# P3_MS.net
KiCad netlist of a schematic drawn in Altium Designer
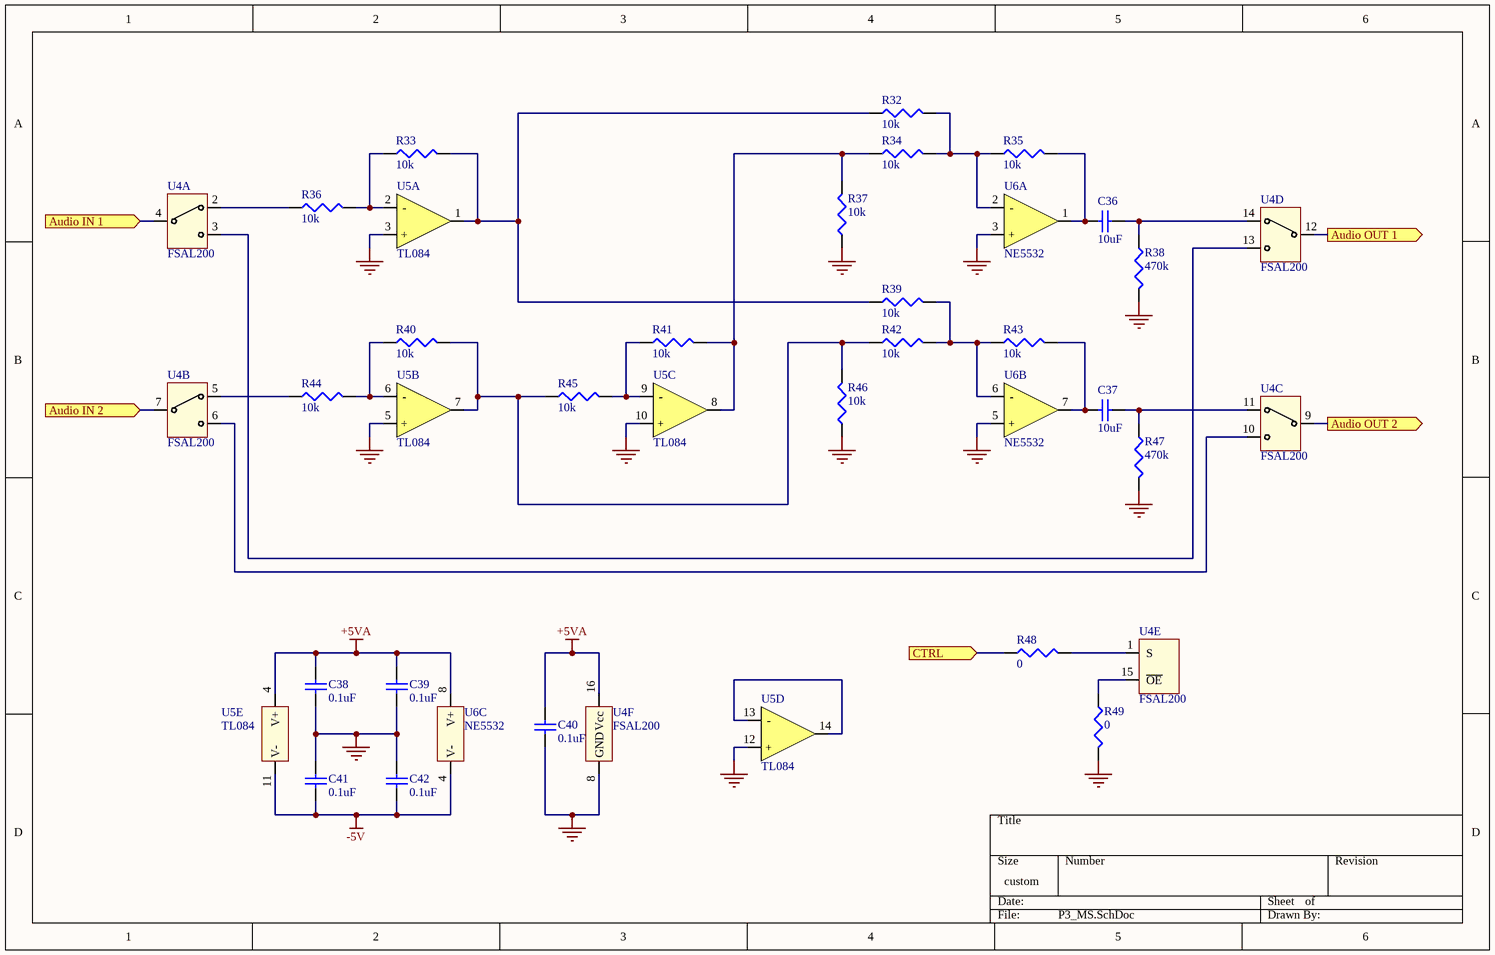
[diagram p0: P3_MS.SchDoc]

(export (version "E")
  (design (tool "Eeschema 10.0.6"))
  (components
    (comp (ref "C36")
      (value "10uF")
      (footprint "CAP 0603 (1608 metric)")
      (description "Capacitor (Semiconductor SIM Model)")
      (libsource (lib "Miscellaneous Devices") (part "Cap Semi"))
    )
    (comp (ref "C37")
      (value "10uF")
      (footprint "CAP 0603 (1608 metric)")
      (description "Capacitor (Semiconductor SIM Model)")
      (libsource (lib "Miscellaneous Devices") (part "Cap Semi"))
    )
    (comp (ref "C38")
      (value "0.1uF")
      (footprint "CAP 0603 (1608 metric)")
      (description "Capacitor (Semiconductor SIM Model)")
      (libsource (lib "Miscellaneous Devices") (part "Cap Semi"))
    )
    (comp (ref "C39")
      (value "0.1uF")
      (footprint "CAP 0603 (1608 metric)")
      (description "Capacitor (Semiconductor SIM Model)")
      (libsource (lib "Miscellaneous Devices") (part "Cap Semi"))
    )
    (comp (ref "C40")
      (value "0.1uF")
      (footprint "CAP 0603 (1608 metric)")
      (description "Capacitor (Semiconductor SIM Model)")
      (libsource (lib "Miscellaneous Devices") (part "Cap Semi"))
    )
    (comp (ref "C41")
      (value "0.1uF")
      (footprint "CAP 0603 (1608 metric)")
      (description "Capacitor (Semiconductor SIM Model)")
      (libsource (lib "Miscellaneous Devices") (part "Cap Semi"))
    )
    (comp (ref "C42")
      (value "0.1uF")
      (footprint "CAP 0603 (1608 metric)")
      (description "Capacitor (Semiconductor SIM Model)")
      (libsource (lib "Miscellaneous Devices") (part "Cap Semi"))
    )
    (comp (ref "R32")
      (value "10k")
      (footprint "RES 0603 (1608 metric)")
      (description "Resistor")
      (libsource (lib "Miscellaneous Devices") (part "Res3"))
    )
    (comp (ref "R33")
      (value "10k")
      (footprint "RES 0603 (1608 metric)")
      (description "Resistor")
      (libsource (lib "Miscellaneous Devices") (part "Res3"))
    )
    (comp (ref "R34")
      (value "10k")
      (footprint "RES 0603 (1608 metric)")
      (description "Resistor")
      (libsource (lib "Miscellaneous Devices") (part "Res3"))
    )
    (comp (ref "R35")
      (value "10k")
      (footprint "RES 0603 (1608 metric)")
      (description "Resistor")
      (libsource (lib "Miscellaneous Devices") (part "Res3"))
    )
    (comp (ref "R36")
      (value "10k")
      (footprint "RES 0603 (1608 metric)")
      (description "Resistor")
      (libsource (lib "Miscellaneous Devices") (part "Res3"))
    )
    (comp (ref "R37")
      (value "10k")
      (footprint "RES 0603 (1608 metric)")
      (description "Resistor")
      (libsource (lib "Miscellaneous Devices") (part "Res3"))
    )
    (comp (ref "R38")
      (value "470k")
      (footprint "RES 0603 (1608 metric)")
      (description "Resistor")
      (libsource (lib "Miscellaneous Devices") (part "Res3"))
    )
    (comp (ref "R39")
      (value "10k")
      (footprint "RES 0603 (1608 metric)")
      (description "Resistor")
      (libsource (lib "Miscellaneous Devices") (part "Res3"))
    )
    (comp (ref "R40")
      (value "10k")
      (footprint "RES 0603 (1608 metric)")
      (description "Resistor")
      (libsource (lib "Miscellaneous Devices") (part "Res3"))
    )
    (comp (ref "R41")
      (value "10k")
      (footprint "RES 0603 (1608 metric)")
      (description "Resistor")
      (libsource (lib "Miscellaneous Devices") (part "Res3"))
    )
    (comp (ref "R42")
      (value "10k")
      (footprint "RES 0603 (1608 metric)")
      (description "Resistor")
      (libsource (lib "Miscellaneous Devices") (part "Res3"))
    )
    (comp (ref "R43")
      (value "10k")
      (footprint "RES 0603 (1608 metric)")
      (description "Resistor")
      (libsource (lib "Miscellaneous Devices") (part "Res3"))
    )
    (comp (ref "R44")
      (value "10k")
      (footprint "RES 0603 (1608 metric)")
      (description "Resistor")
      (libsource (lib "Miscellaneous Devices") (part "Res3"))
    )
    (comp (ref "R45")
      (value "10k")
      (footprint "RES 0603 (1608 metric)")
      (description "Resistor")
      (libsource (lib "Miscellaneous Devices") (part "Res3"))
    )
    (comp (ref "R46")
      (value "10k")
      (footprint "RES 0603 (1608 metric)")
      (description "Resistor")
      (libsource (lib "Miscellaneous Devices") (part "Res3"))
    )
    (comp (ref "R47")
      (value "470k")
      (footprint "RES 0603 (1608 metric)")
      (description "Resistor")
      (libsource (lib "Miscellaneous Devices") (part "Res3"))
    )
    (comp (ref "R48")
      (value "0")
      (footprint "RES 0603 (1608 metric)")
      (description "Resistor")
      (libsource (lib "Miscellaneous Devices") (part "Res3"))
    )
    (comp (ref "R49")
      (value "0")
      (footprint "RES 0603 (1608 metric)")
      (description "Resistor")
      (libsource (lib "Miscellaneous Devices") (part "Res3"))
    )
    (comp (ref "U4")
      (value "FSAL200")
      (description "Quad 2:1 Multiplexer")
      (libsource (lib "FilterPoC") (part "FSAL200"))
    )
    (comp (ref "U5")
      (value "TL084")
      (description "Quad Audio OpAmp")
      (libsource (lib "FilterPoC") (part "TL084"))
    )
    (comp (ref "U6")
      (value "NE5532")
      (description "Dual Audio OpAmp")
      (libsource (lib "FilterPoC") (part "NE5532"))
    )
  )
  (nets
    (net (code "1") (name "+5VA") (class "Default")
      (node (ref "C38") (pin "1") (pinfunction "1_1") (pintype "passive"))
      (node (ref "C39") (pin "1") (pinfunction "1_1") (pintype "passive"))
      (node (ref "C40") (pin "1") (pinfunction "1_1") (pintype "passive"))
      (node (ref "U4") (pin "16") (pinfunction "Vcc_16") (pintype "power_in"))
      (node (ref "U5") (pin "4") (pinfunction "V+_4") (pintype "power_in"))
      (node (ref "U6") (pin "8") (pinfunction "V+_8") (pintype "power_in"))
    )
    (net (code "2") (name "-5V") (class "Default")
      (node (ref "C41") (pin "2") (pinfunction "2_2") (pintype "passive"))
      (node (ref "C42") (pin "2") (pinfunction "2_2") (pintype "passive"))
      (node (ref "U5") (pin "11") (pinfunction "V-_11") (pintype "power_in"))
      (node (ref "U6") (pin "4") (pinfunction "V-_4") (pintype "power_in"))
    )
    (net (code "3") (name "/Audio IN 1") (class "Default")
      (node (ref "U4") (pin "4") (pinfunction "A_4") (pintype "passive"))
    )
    (net (code "4") (name "/Audio IN 2") (class "Default")
      (node (ref "U4") (pin "7") (pinfunction "A_7") (pintype "passive"))
    )
    (net (code "5") (name "/Audio OUT 1") (class "Default")
      (node (ref "U4") (pin "12") (pinfunction "A_12") (pintype "passive"))
    )
    (net (code "6") (name "/Audio OUT 2") (class "Default")
      (node (ref "U4") (pin "9") (pinfunction "A_9") (pintype "passive"))
    )
    (net (code "7") (name "/CTRL") (class "Default")
      (node (ref "R48") (pin "1") (pinfunction "1_1") (pintype "passive"))
    )
    (net (code "8") (name "GND") (class "Default")
      (node (ref "C38") (pin "2") (pinfunction "2_2") (pintype "passive"))
      (node (ref "C39") (pin "2") (pinfunction "2_2") (pintype "passive"))
      (node (ref "C40") (pin "2") (pinfunction "2_2") (pintype "passive"))
      (node (ref "C41") (pin "1") (pinfunction "1_1") (pintype "passive"))
      (node (ref "C42") (pin "1") (pinfunction "1_1") (pintype "passive"))
      (node (ref "R37") (pin "1") (pinfunction "1_1") (pintype "passive"))
      (node (ref "R38") (pin "2") (pinfunction "2_2") (pintype "passive"))
      (node (ref "R46") (pin "1") (pinfunction "1_1") (pintype "passive"))
      (node (ref "R47") (pin "2") (pinfunction "2_2") (pintype "passive"))
      (node (ref "R49") (pin "2") (pinfunction "2_2") (pintype "passive"))
      (node (ref "U4") (pin "8") (pinfunction "GND_8") (pintype "power_in"))
      (node (ref "U5") (pin "10") (pinfunction "+_10") (pintype "passive"))
      (node (ref "U5") (pin "12") (pinfunction "+_12") (pintype "passive"))
      (node (ref "U5") (pin "3") (pinfunction "+_3") (pintype "passive"))
      (node (ref "U5") (pin "5") (pinfunction "+_5") (pintype "passive"))
      (node (ref "U6") (pin "3") (pinfunction "+_3") (pintype "passive"))
      (node (ref "U6") (pin "5") (pinfunction "+_5") (pintype "passive"))
    )
    (net (code "9") (name "Net-(U4A-B1)") (class "Default")
      (node (ref "R36") (pin "1") (pinfunction "1_1") (pintype "passive"))
      (node (ref "U4") (pin "2") (pinfunction "B1_2") (pintype "passive"))
    )
    (net (code "10") (name "Net-(U4A-B2)") (class "Default")
      (node (ref "U4") (pin "13") (pinfunction "B2_13") (pintype "passive"))
      (node (ref "U4") (pin "3") (pinfunction "B2_3") (pintype "passive"))
    )
    (net (code "11") (name "Net-(U4B-B1)") (class "Default")
      (node (ref "R44") (pin "1") (pinfunction "1_1") (pintype "passive"))
      (node (ref "U4") (pin "5") (pinfunction "B1_5") (pintype "passive"))
    )
    (net (code "12") (name "Net-(U4B-B2)") (class "Default")
      (node (ref "U4") (pin "10") (pinfunction "B2_10") (pintype "passive"))
      (node (ref "U4") (pin "6") (pinfunction "B2_6") (pintype "passive"))
    )
    (net (code "13") (name "Net-(U4C-B1)") (class "Default")
      (node (ref "C37") (pin "1") (pinfunction "1_1") (pintype "passive"))
      (node (ref "R47") (pin "1") (pinfunction "1_1") (pintype "passive"))
      (node (ref "U4") (pin "11") (pinfunction "B1_11") (pintype "passive"))
    )
    (net (code "14") (name "Net-(U4D-B1)") (class "Default")
      (node (ref "C36") (pin "1") (pinfunction "1_1") (pintype "passive"))
      (node (ref "R38") (pin "1") (pinfunction "1_1") (pintype "passive"))
      (node (ref "U4") (pin "14") (pinfunction "B1_14") (pintype "passive"))
    )
    (net (code "15") (name "Net-(U4E-S)") (class "Default")
      (node (ref "R48") (pin "2") (pinfunction "2_2") (pintype "passive"))
      (node (ref "U4") (pin "1") (pinfunction "S_1") (pintype "passive"))
    )
    (net (code "16") (name "Net-(U4E-~{OE})") (class "Default")
      (node (ref "R49") (pin "1") (pinfunction "1_1") (pintype "passive"))
      (node (ref "U4") (pin "15") (pinfunction "~{OE}_15") (pintype "passive"))
    )
    (net (code "17") (name "Net-(U5A--)") (class "Default")
      (node (ref "R33") (pin "1") (pinfunction "1_1") (pintype "passive"))
      (node (ref "R36") (pin "2") (pinfunction "2_2") (pintype "passive"))
      (node (ref "U5") (pin "2") (pinfunction "-_2") (pintype "passive"))
    )
    (net (code "18") (name "Net-(U5A-OUT)") (class "Default")
      (node (ref "R32") (pin "1") (pinfunction "1_1") (pintype "passive"))
      (node (ref "R33") (pin "2") (pinfunction "2_2") (pintype "passive"))
      (node (ref "R39") (pin "1") (pinfunction "1_1") (pintype "passive"))
      (node (ref "U5") (pin "1") (pinfunction "OUT_1") (pintype "passive"))
    )
    (net (code "19") (name "Net-(U5B--)") (class "Default")
      (node (ref "R40") (pin "1") (pinfunction "1_1") (pintype "passive"))
      (node (ref "R44") (pin "2") (pinfunction "2_2") (pintype "passive"))
      (node (ref "U5") (pin "6") (pinfunction "-_6") (pintype "passive"))
    )
    (net (code "20") (name "Net-(U5B-OUT)") (class "Default")
      (node (ref "R40") (pin "2") (pinfunction "2_2") (pintype "passive"))
      (node (ref "R42") (pin "1") (pinfunction "1_1") (pintype "passive"))
      (node (ref "R45") (pin "1") (pinfunction "1_1") (pintype "passive"))
      (node (ref "R46") (pin "2") (pinfunction "2_2") (pintype "passive"))
      (node (ref "U5") (pin "7") (pinfunction "OUT_7") (pintype "passive"))
    )
    (net (code "21") (name "Net-(U5C--)") (class "Default")
      (node (ref "R41") (pin "1") (pinfunction "1_1") (pintype "passive"))
      (node (ref "R45") (pin "2") (pinfunction "2_2") (pintype "passive"))
      (node (ref "U5") (pin "9") (pinfunction "-_9") (pintype "passive"))
    )
    (net (code "22") (name "Net-(U5C-OUT)") (class "Default")
      (node (ref "R34") (pin "1") (pinfunction "1_1") (pintype "passive"))
      (node (ref "R37") (pin "2") (pinfunction "2_2") (pintype "passive"))
      (node (ref "R41") (pin "2") (pinfunction "2_2") (pintype "passive"))
      (node (ref "U5") (pin "8") (pinfunction "OUT_8") (pintype "passive"))
    )
    (net (code "23") (name "Net-(U5D--)") (class "Default")
      (node (ref "U5") (pin "13") (pinfunction "-_13") (pintype "passive"))
      (node (ref "U5") (pin "14") (pinfunction "OUT_14") (pintype "passive"))
    )
    (net (code "24") (name "Net-(U6A--)") (class "Default")
      (node (ref "R32") (pin "2") (pinfunction "2_2") (pintype "passive"))
      (node (ref "R34") (pin "2") (pinfunction "2_2") (pintype "passive"))
      (node (ref "R35") (pin "1") (pinfunction "1_1") (pintype "passive"))
      (node (ref "U6") (pin "2") (pinfunction "-_2") (pintype "passive"))
    )
    (net (code "25") (name "Net-(U6A-OUT)") (class "Default")
      (node (ref "C36") (pin "2") (pinfunction "2_2") (pintype "passive"))
      (node (ref "R35") (pin "2") (pinfunction "2_2") (pintype "passive"))
      (node (ref "U6") (pin "1") (pinfunction "OUT_1") (pintype "passive"))
    )
    (net (code "26") (name "Net-(U6B--)") (class "Default")
      (node (ref "R39") (pin "2") (pinfunction "2_2") (pintype "passive"))
      (node (ref "R42") (pin "2") (pinfunction "2_2") (pintype "passive"))
      (node (ref "R43") (pin "1") (pinfunction "1_1") (pintype "passive"))
      (node (ref "U6") (pin "6") (pinfunction "-_6") (pintype "passive"))
    )
    (net (code "27") (name "Net-(U6B-OUT)") (class "Default")
      (node (ref "C37") (pin "2") (pinfunction "2_2") (pintype "passive"))
      (node (ref "R43") (pin "2") (pinfunction "2_2") (pintype "passive"))
      (node (ref "U6") (pin "7") (pinfunction "OUT_7") (pintype "passive"))
    )
  )
)
